# 03_MCU.net
KiCad netlist of a schematic drawn in Altium Designer
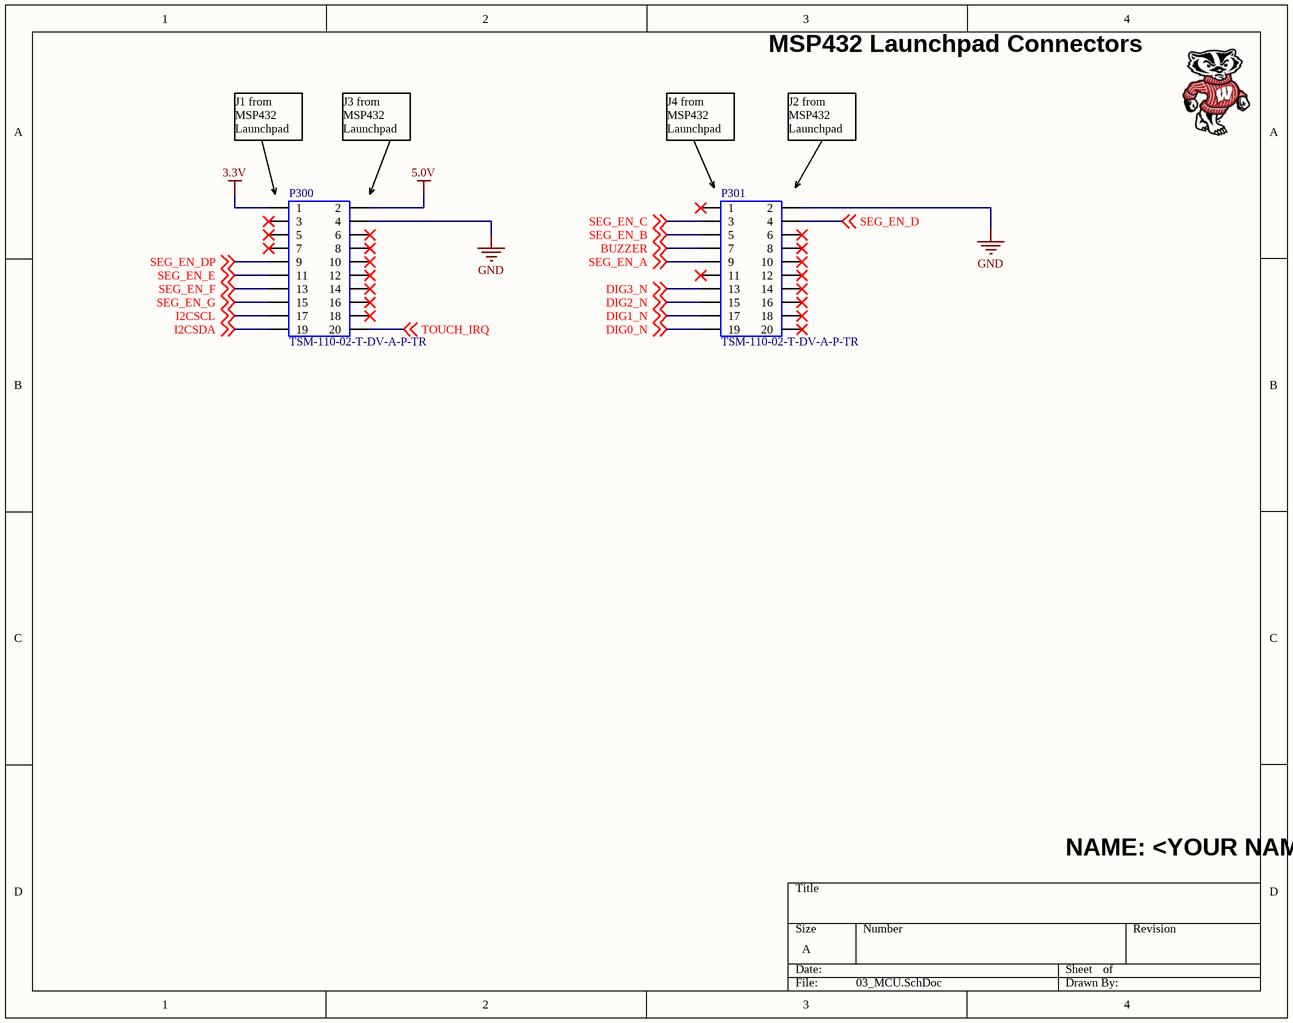
[diagram p0: 03_MCU.SchDoc]

(export (version "E")
  (design (tool "Eeschema 10.0.6"))
  (components
    (comp (ref "P300")
      (value "20 Pin SMD")
      (footprint "TMS-110-01-T-DV-A")
      (description "Conn Unshrouded Header HDR 20 POS 2.54mm Solder ST SMD Tube")
      (fields (field (name "MANUFACTURER PART NUMBER") "TSM-110-02-T-DV-A-P-TR"))
      (libsource (lib "Connectors") (part "TSM-110-02-T-DV-A"))
    )
    (comp (ref "P301")
      (value "20 Pin SMD")
      (footprint "TMS-110-01-T-DV-A")
      (description "Conn Unshrouded Header HDR 20 POS 2.54mm Solder ST SMD Tube")
      (fields (field (name "MANUFACTURER PART NUMBER") "TSM-110-02-T-DV-A-P-TR"))
      (libsource (lib "Connectors") (part "TSM-110-02-T-DV-A"))
    )
  )
  (nets
    (net (code "1") (name "3.3V") (class "Default")
      (node (ref "P300") (pin "1") (pinfunction "1_1") (pintype "passive"))
    )
    (net (code "2") (name "5.0V") (class "Default")
      (node (ref "P300") (pin "2") (pinfunction "2_2") (pintype "passive"))
    )
    (net (code "3") (name "BUZZER") (class "Default")
      (node (ref "P301") (pin "7") (pinfunction "7_7") (pintype "passive"))
    )
    (net (code "4") (name "DIG0_N") (class "Default")
      (node (ref "P301") (pin "19") (pinfunction "19_19") (pintype "passive"))
    )
    (net (code "5") (name "DIG1_N") (class "Default")
      (node (ref "P301") (pin "17") (pinfunction "17_17") (pintype "passive"))
    )
    (net (code "6") (name "DIG2_N") (class "Default")
      (node (ref "P301") (pin "15") (pinfunction "15_15") (pintype "passive"))
    )
    (net (code "7") (name "DIG3_N") (class "Default")
      (node (ref "P301") (pin "13") (pinfunction "13_13") (pintype "passive"))
    )
    (net (code "8") (name "GND") (class "Default")
      (node (ref "P300") (pin "4") (pinfunction "4_4") (pintype "passive"))
      (node (ref "P301") (pin "2") (pinfunction "2_2") (pintype "passive"))
    )
    (net (code "9") (name "I2CSCL") (class "Default")
      (node (ref "P300") (pin "17") (pinfunction "17_17") (pintype "passive"))
    )
    (net (code "10") (name "I2CSDA") (class "Default")
      (node (ref "P300") (pin "19") (pinfunction "19_19") (pintype "passive"))
    )
    (net (code "11") (name "SEG_EN_A") (class "Default")
      (node (ref "P301") (pin "9") (pinfunction "9_9") (pintype "passive"))
    )
    (net (code "12") (name "SEG_EN_B") (class "Default")
      (node (ref "P301") (pin "5") (pinfunction "5_5") (pintype "passive"))
    )
    (net (code "13") (name "SEG_EN_C") (class "Default")
      (node (ref "P301") (pin "3") (pinfunction "3_3") (pintype "passive"))
    )
    (net (code "14") (name "SEG_EN_D") (class "Default")
      (node (ref "P301") (pin "4") (pinfunction "4_4") (pintype "passive"))
    )
    (net (code "15") (name "SEG_EN_DP") (class "Default")
      (node (ref "P300") (pin "9") (pinfunction "9_9") (pintype "passive"))
    )
    (net (code "16") (name "SEG_EN_E") (class "Default")
      (node (ref "P300") (pin "11") (pinfunction "11_11") (pintype "passive"))
    )
    (net (code "17") (name "SEG_EN_F") (class "Default")
      (node (ref "P300") (pin "13") (pinfunction "13_13") (pintype "passive"))
    )
    (net (code "18") (name "SEG_EN_G") (class "Default")
      (node (ref "P300") (pin "15") (pinfunction "15_15") (pintype "passive"))
    )
    (net (code "19") (name "TOUCH_IRQ") (class "Default")
      (node (ref "P300") (pin "20") (pinfunction "20_20") (pintype "passive"))
    )
    (net (code "20") (name "unconnected-(P300-Pad3)") (class "Default")
      (node (ref "P300") (pin "3") (pinfunction "3_3") (pintype "passive+no_connect"))
    )
    (net (code "21") (name "unconnected-(P300-Pad5)") (class "Default")
      (node (ref "P300") (pin "5") (pinfunction "5_5") (pintype "passive+no_connect"))
    )
    (net (code "22") (name "unconnected-(P300-Pad6)") (class "Default")
      (node (ref "P300") (pin "6") (pinfunction "6_6") (pintype "passive+no_connect"))
    )
    (net (code "23") (name "unconnected-(P300-Pad7)") (class "Default")
      (node (ref "P300") (pin "7") (pinfunction "7_7") (pintype "passive+no_connect"))
    )
    (net (code "24") (name "unconnected-(P300-Pad8)") (class "Default")
      (node (ref "P300") (pin "8") (pinfunction "8_8") (pintype "passive+no_connect"))
    )
    (net (code "25") (name "unconnected-(P300-Pad10)") (class "Default")
      (node (ref "P300") (pin "10") (pinfunction "10_10") (pintype "passive+no_connect"))
    )
    (net (code "26") (name "unconnected-(P300-Pad12)") (class "Default")
      (node (ref "P300") (pin "12") (pinfunction "12_12") (pintype "passive+no_connect"))
    )
    (net (code "27") (name "unconnected-(P300-Pad14)") (class "Default")
      (node (ref "P300") (pin "14") (pinfunction "14_14") (pintype "passive+no_connect"))
    )
    (net (code "28") (name "unconnected-(P300-Pad16)") (class "Default")
      (node (ref "P300") (pin "16") (pinfunction "16_16") (pintype "passive+no_connect"))
    )
    (net (code "29") (name "unconnected-(P300-Pad18)") (class "Default")
      (node (ref "P300") (pin "18") (pinfunction "18_18") (pintype "passive+no_connect"))
    )
    (net (code "30") (name "unconnected-(P301-Pad1)") (class "Default")
      (node (ref "P301") (pin "1") (pinfunction "1_1") (pintype "passive+no_connect"))
    )
    (net (code "31") (name "unconnected-(P301-Pad6)") (class "Default")
      (node (ref "P301") (pin "6") (pinfunction "6_6") (pintype "passive+no_connect"))
    )
    (net (code "32") (name "unconnected-(P301-Pad8)") (class "Default")
      (node (ref "P301") (pin "8") (pinfunction "8_8") (pintype "passive+no_connect"))
    )
    (net (code "33") (name "unconnected-(P301-Pad10)") (class "Default")
      (node (ref "P301") (pin "10") (pinfunction "10_10") (pintype "passive+no_connect"))
    )
    (net (code "34") (name "unconnected-(P301-Pad11)") (class "Default")
      (node (ref "P301") (pin "11") (pinfunction "11_11") (pintype "passive+no_connect"))
    )
    (net (code "35") (name "unconnected-(P301-Pad12)") (class "Default")
      (node (ref "P301") (pin "12") (pinfunction "12_12") (pintype "passive+no_connect"))
    )
    (net (code "36") (name "unconnected-(P301-Pad14)") (class "Default")
      (node (ref "P301") (pin "14") (pinfunction "14_14") (pintype "passive+no_connect"))
    )
    (net (code "37") (name "unconnected-(P301-Pad16)") (class "Default")
      (node (ref "P301") (pin "16") (pinfunction "16_16") (pintype "passive+no_connect"))
    )
    (net (code "38") (name "unconnected-(P301-Pad18)") (class "Default")
      (node (ref "P301") (pin "18") (pinfunction "18_18") (pintype "passive+no_connect"))
    )
    (net (code "39") (name "unconnected-(P301-Pad20)") (class "Default")
      (node (ref "P301") (pin "20") (pinfunction "20_20") (pintype "passive+no_connect"))
    )
  )
)
